# Current_Sens.net
KiCad netlist of a schematic drawn in Altium Designer
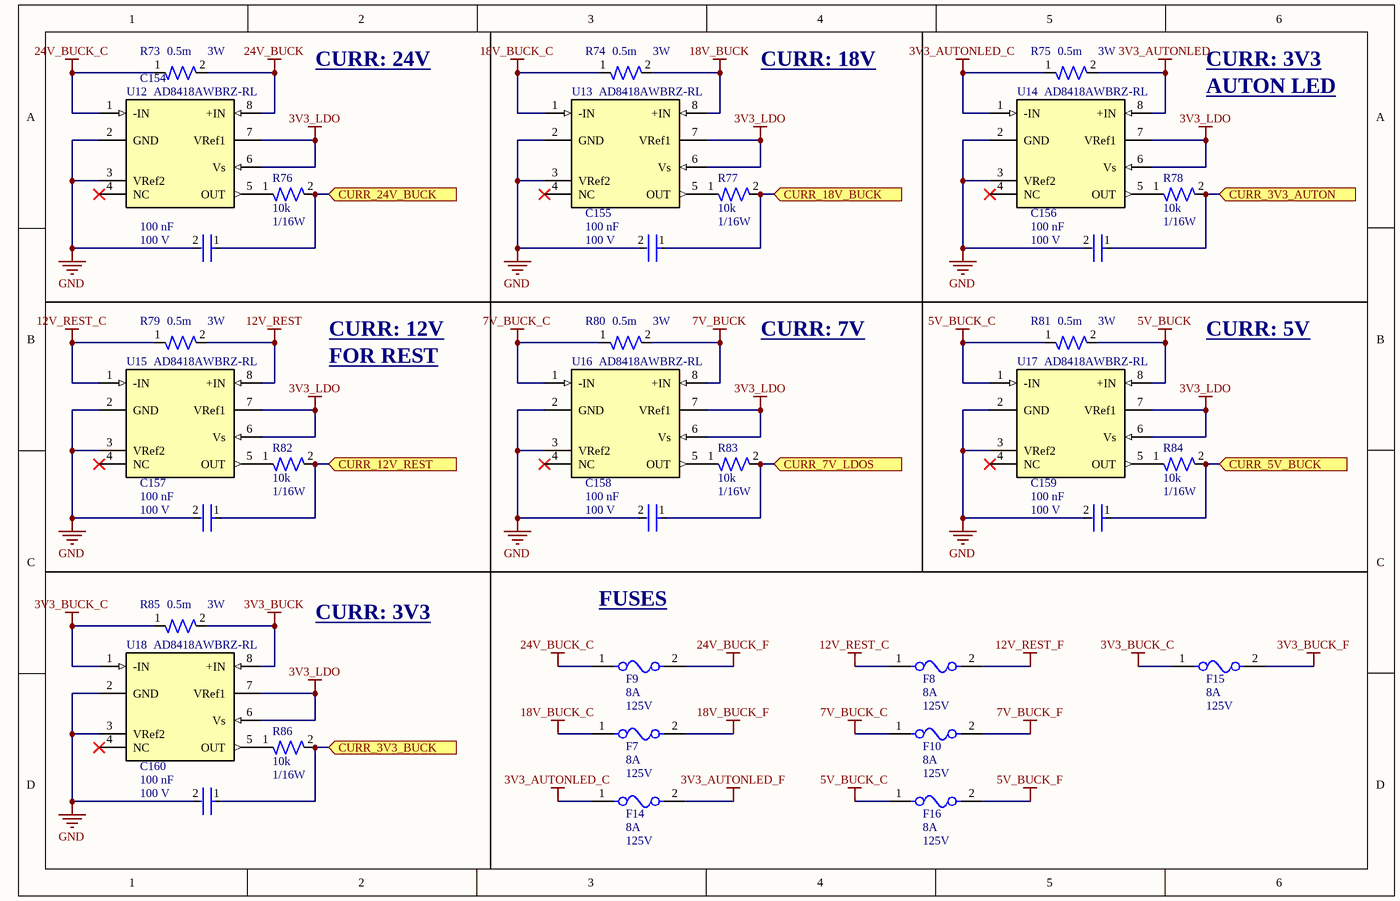
[diagram p0: Current_Sens.SchDoc]

(export (version "E")
  (design (tool "Eeschema 10.0.6"))
  (components
    (comp (ref "C154")
      (value "CC0603KRX7R0BB104")
      (footprint "CAP-0603")
      (description "CAP CER 0.1UF 100V X7R 0603")
      (fields (field (name "CAPACITANCE") "100 nF") (field (name "VOLTAGE") "100 V"))
      (libsource (lib "JLC_25") (part "CAP-100N-0001"))
    )
    (comp (ref "C155")
      (value "CC0603KRX7R0BB104")
      (footprint "CAP-0603")
      (description "CAP CER 0.1UF 100V X7R 0603")
      (fields (field (name "CAPACITANCE") "100 nF") (field (name "VOLTAGE") "100 V"))
      (libsource (lib "JLC_25") (part "CAP-100N-0001"))
    )
    (comp (ref "C156")
      (value "CC0603KRX7R0BB104")
      (footprint "CAP-0603")
      (description "CAP CER 0.1UF 100V X7R 0603")
      (fields (field (name "CAPACITANCE") "100 nF") (field (name "VOLTAGE") "100 V"))
      (libsource (lib "JLC_25") (part "CAP-100N-0001"))
    )
    (comp (ref "C157")
      (value "CC0603KRX7R0BB104")
      (footprint "CAP-0603")
      (description "CAP CER 0.1UF 100V X7R 0603")
      (fields (field (name "CAPACITANCE") "100 nF") (field (name "VOLTAGE") "100 V"))
      (libsource (lib "JLC_25") (part "CAP-100N-0001"))
    )
    (comp (ref "C158")
      (value "CC0603KRX7R0BB104")
      (footprint "CAP-0603")
      (description "CAP CER 0.1UF 100V X7R 0603")
      (fields (field (name "CAPACITANCE") "100 nF") (field (name "VOLTAGE") "100 V"))
      (libsource (lib "JLC_25") (part "CAP-100N-0001"))
    )
    (comp (ref "C159")
      (value "CC0603KRX7R0BB104")
      (footprint "CAP-0603")
      (description "CAP CER 0.1UF 100V X7R 0603")
      (fields (field (name "CAPACITANCE") "100 nF") (field (name "VOLTAGE") "100 V"))
      (libsource (lib "JLC_25") (part "CAP-100N-0001"))
    )
    (comp (ref "C160")
      (value "CC0603KRX7R0BB104")
      (footprint "CAP-0603")
      (description "CAP CER 0.1UF 100V X7R 0603")
      (fields (field (name "CAPACITANCE") "100 nF") (field (name "VOLTAGE") "100 V"))
      (libsource (lib "JLC_25") (part "CAP-100N-0001"))
    )
    (comp (ref "F7")
      (value "01550900M")
      (footprint "FUSE-0001")
      (description "FUSE BLOK CARTRIDGE 125V 10A SMD")
      (fields (field (name "FUSE CURRENT") "8A") (field (name "VOLTAGE RATING") "125V"))
      (libsource (lib "JLC_25") (part "FUSE-0001"))
    )
    (comp (ref "F8")
      (value "01550900M")
      (footprint "FUSE-0001")
      (description "FUSE BLOK CARTRIDGE 125V 10A SMD")
      (fields (field (name "FUSE CURRENT") "8A") (field (name "VOLTAGE RATING") "125V"))
      (libsource (lib "JLC_25") (part "FUSE-0001"))
    )
    (comp (ref "F9")
      (value "01550900M")
      (footprint "FUSE-0001")
      (description "FUSE BLOK CARTRIDGE 125V 10A SMD")
      (fields (field (name "FUSE CURRENT") "8A") (field (name "VOLTAGE RATING") "125V"))
      (libsource (lib "JLC_25") (part "FUSE-0001"))
    )
    (comp (ref "F10")
      (value "01550900M")
      (footprint "FUSE-0001")
      (description "FUSE BLOK CARTRIDGE 125V 10A SMD")
      (fields (field (name "FUSE CURRENT") "8A") (field (name "VOLTAGE RATING") "125V"))
      (libsource (lib "JLC_25") (part "FUSE-0001"))
    )
    (comp (ref "F14")
      (value "01550900M")
      (footprint "FUSE-0001")
      (description "FUSE BLOK CARTRIDGE 125V 10A SMD")
      (fields (field (name "FUSE CURRENT") "8A") (field (name "VOLTAGE RATING") "125V"))
      (libsource (lib "JLC_25") (part "FUSE-0001"))
    )
    (comp (ref "F15")
      (value "01550900M")
      (footprint "FUSE-0001")
      (description "FUSE BLOK CARTRIDGE 125V 10A SMD")
      (fields (field (name "FUSE CURRENT") "8A") (field (name "VOLTAGE RATING") "125V"))
      (libsource (lib "JLC_25") (part "FUSE-0001"))
    )
    (comp (ref "F16")
      (value "01550900M")
      (footprint "FUSE-0001")
      (description "FUSE BLOK CARTRIDGE 125V 10A SMD")
      (fields (field (name "FUSE CURRENT") "8A") (field (name "VOLTAGE RATING") "125V"))
      (libsource (lib "JLC_25") (part "FUSE-0001"))
    )
    (comp (ref "R73")
      (value "CSNL2512FTL500")
      (footprint "RES-2512")
      (description "2512 Chip Resistor - Surface Mount ROHS")
      (fields (field (name "TOLERANCE") "1%") (field (name "POWER") "3W") (field (name "RESISTANCE") "0.5m"))
      (libsource (lib "JLC_25") (part "RES-0.5m-0001"))
    )
    (comp (ref "R74")
      (value "CSNL2512FTL500")
      (footprint "RES-2512")
      (description "2512 Chip Resistor - Surface Mount ROHS")
      (fields (field (name "TOLERANCE") "1%") (field (name "POWER") "3W") (field (name "RESISTANCE") "0.5m"))
      (libsource (lib "JLC_25") (part "RES-0.5m-0001"))
    )
    (comp (ref "R75")
      (value "CSNL2512FTL500")
      (footprint "RES-2512")
      (description "2512 Chip Resistor - Surface Mount ROHS")
      (fields (field (name "TOLERANCE") "1%") (field (name "POWER") "3W") (field (name "RESISTANCE") "0.5m"))
      (libsource (lib "JLC_25") (part "RES-0.5m-0001"))
    )
    (comp (ref "R76")
      (value "RC0402FR-0710KL")
      (footprint "RES-0402")
      (description "RES 10K OHM 1% 1/16W 0402")
      (fields
        (field (name "TOLERANCE") "1%")
        (field (name "RESISTANCE") "10k")
        (field (name "POWER") "1/16W")
      )
      (libsource (lib "JLC_25") (part "RES-10k-0001"))
    )
    (comp (ref "R77")
      (value "RC0402FR-0710KL")
      (footprint "RES-0402")
      (description "RES 10K OHM 1% 1/16W 0402")
      (fields
        (field (name "TOLERANCE") "1%")
        (field (name "RESISTANCE") "10k")
        (field (name "POWER") "1/16W")
      )
      (libsource (lib "JLC_25") (part "RES-10k-0001"))
    )
    (comp (ref "R78")
      (value "RC0402FR-0710KL")
      (footprint "RES-0402")
      (description "RES 10K OHM 1% 1/16W 0402")
      (fields
        (field (name "TOLERANCE") "1%")
        (field (name "RESISTANCE") "10k")
        (field (name "POWER") "1/16W")
      )
      (libsource (lib "JLC_25") (part "RES-10k-0001"))
    )
    (comp (ref "R79")
      (value "CSNL2512FTL500")
      (footprint "RES-2512")
      (description "2512 Chip Resistor - Surface Mount ROHS")
      (fields (field (name "TOLERANCE") "1%") (field (name "POWER") "3W") (field (name "RESISTANCE") "0.5m"))
      (libsource (lib "JLC_25") (part "RES-0.5m-0001"))
    )
    (comp (ref "R80")
      (value "CSNL2512FTL500")
      (footprint "RES-2512")
      (description "2512 Chip Resistor - Surface Mount ROHS")
      (fields (field (name "TOLERANCE") "1%") (field (name "POWER") "3W") (field (name "RESISTANCE") "0.5m"))
      (libsource (lib "JLC_25") (part "RES-0.5m-0001"))
    )
    (comp (ref "R81")
      (value "CSNL2512FTL500")
      (footprint "RES-2512")
      (description "2512 Chip Resistor - Surface Mount ROHS")
      (fields (field (name "TOLERANCE") "1%") (field (name "POWER") "3W") (field (name "RESISTANCE") "0.5m"))
      (libsource (lib "JLC_25") (part "RES-0.5m-0001"))
    )
    (comp (ref "R82")
      (value "RC0402FR-0710KL")
      (footprint "RES-0402")
      (description "RES 10K OHM 1% 1/16W 0402")
      (fields
        (field (name "TOLERANCE") "1%")
        (field (name "RESISTANCE") "10k")
        (field (name "POWER") "1/16W")
      )
      (libsource (lib "JLC_25") (part "RES-10k-0001"))
    )
    (comp (ref "R83")
      (value "RC0402FR-0710KL")
      (footprint "RES-0402")
      (description "RES 10K OHM 1% 1/16W 0402")
      (fields
        (field (name "TOLERANCE") "1%")
        (field (name "RESISTANCE") "10k")
        (field (name "POWER") "1/16W")
      )
      (libsource (lib "JLC_25") (part "RES-10k-0001"))
    )
    (comp (ref "R84")
      (value "RC0402FR-0710KL")
      (footprint "RES-0402")
      (description "RES 10K OHM 1% 1/16W 0402")
      (fields
        (field (name "TOLERANCE") "1%")
        (field (name "RESISTANCE") "10k")
        (field (name "POWER") "1/16W")
      )
      (libsource (lib "JLC_25") (part "RES-10k-0001"))
    )
    (comp (ref "R85")
      (value "CSNL2512FTL500")
      (footprint "RES-2512")
      (description "2512 Chip Resistor - Surface Mount ROHS")
      (fields (field (name "TOLERANCE") "1%") (field (name "POWER") "3W") (field (name "RESISTANCE") "0.5m"))
      (libsource (lib "JLC_25") (part "RES-0.5m-0001"))
    )
    (comp (ref "R86")
      (value "RC0402FR-0710KL")
      (footprint "RES-0402")
      (description "RES 10K OHM 1% 1/16W 0402")
      (fields
        (field (name "TOLERANCE") "1%")
        (field (name "RESISTANCE") "10k")
        (field (name "POWER") "1/16W")
      )
      (libsource (lib "JLC_25") (part "RES-10k-0001"))
    )
    (comp (ref "U12")
      (value "AD8418AWBRZ-RL")
      (footprint "IC-CURR")
      (description "Current Sense Amplifier 1 Circuit 8-MSOP")
      (libsource (lib "JLC_25") (part "IC-CURR-0001"))
    )
    (comp (ref "U13")
      (value "AD8418AWBRZ-RL")
      (footprint "IC-CURR")
      (description "Current Sense Amplifier 1 Circuit 8-MSOP")
      (libsource (lib "JLC_25") (part "IC-CURR-0001"))
    )
    (comp (ref "U14")
      (value "AD8418AWBRZ-RL")
      (footprint "IC-CURR")
      (description "Current Sense Amplifier 1 Circuit 8-MSOP")
      (libsource (lib "JLC_25") (part "IC-CURR-0001"))
    )
    (comp (ref "U15")
      (value "AD8418AWBRZ-RL")
      (footprint "IC-CURR")
      (description "Current Sense Amplifier 1 Circuit 8-MSOP")
      (libsource (lib "JLC_25") (part "IC-CURR-0001"))
    )
    (comp (ref "U16")
      (value "AD8418AWBRZ-RL")
      (footprint "IC-CURR")
      (description "Current Sense Amplifier 1 Circuit 8-MSOP")
      (libsource (lib "JLC_25") (part "IC-CURR-0001"))
    )
    (comp (ref "U17")
      (value "AD8418AWBRZ-RL")
      (footprint "IC-CURR")
      (description "Current Sense Amplifier 1 Circuit 8-MSOP")
      (libsource (lib "JLC_25") (part "IC-CURR-0001"))
    )
    (comp (ref "U18")
      (value "AD8418AWBRZ-RL")
      (footprint "IC-CURR")
      (description "Current Sense Amplifier 1 Circuit 8-MSOP")
      (libsource (lib "JLC_25") (part "IC-CURR-0001"))
    )
  )
  (nets
    (net (code "1") (name "/CURR_3V3_AUTON") (class "Default")
      (node (ref "C156") (pin "1") (pinfunction "1_1") (pintype "passive"))
      (node (ref "R78") (pin "2") (pinfunction "2_2") (pintype "passive"))
    )
    (net (code "2") (name "/CURR_3V3_BUCK") (class "Default")
      (node (ref "C160") (pin "1") (pinfunction "1_1") (pintype "passive"))
      (node (ref "R86") (pin "2") (pinfunction "2_2") (pintype "passive"))
    )
    (net (code "3") (name "/CURR_5V_BUCK") (class "Default")
      (node (ref "C159") (pin "1") (pinfunction "1_1") (pintype "passive"))
      (node (ref "R84") (pin "2") (pinfunction "2_2") (pintype "passive"))
    )
    (net (code "4") (name "/CURR_7V_LDOS") (class "Default")
      (node (ref "C158") (pin "1") (pinfunction "1_1") (pintype "passive"))
      (node (ref "R83") (pin "2") (pinfunction "2_2") (pintype "passive"))
    )
    (net (code "5") (name "/CURR_12V_REST") (class "Default")
      (node (ref "C157") (pin "1") (pinfunction "1_1") (pintype "passive"))
      (node (ref "R82") (pin "2") (pinfunction "2_2") (pintype "passive"))
    )
    (net (code "6") (name "/CURR_18V_BUCK") (class "Default")
      (node (ref "C155") (pin "1") (pinfunction "1_1") (pintype "passive"))
      (node (ref "R77") (pin "2") (pinfunction "2_2") (pintype "passive"))
    )
    (net (code "7") (name "/CURR_24V_BUCK") (class "Default")
      (node (ref "C154") (pin "1") (pinfunction "1_1") (pintype "passive"))
      (node (ref "R76") (pin "2") (pinfunction "2_2") (pintype "passive"))
    )
    (net (code "8") (name "3V3_AUTONLED") (class "Default")
      (node (ref "R75") (pin "2") (pinfunction "2_2") (pintype "passive"))
      (node (ref "U14") (pin "8") (pinfunction "+IN_8") (pintype "input"))
    )
    (net (code "9") (name "3V3_AUTONLED_C") (class "Default")
      (node (ref "F14") (pin "1") (pinfunction "1_1") (pintype "passive"))
      (node (ref "R75") (pin "1") (pinfunction "1_1") (pintype "passive"))
      (node (ref "U14") (pin "1") (pinfunction "-IN_1") (pintype "input"))
    )
    (net (code "10") (name "3V3_AUTONLED_F") (class "Default")
      (node (ref "F14") (pin "2") (pinfunction "2_2") (pintype "passive"))
    )
    (net (code "11") (name "3V3_BUCK") (class "Default")
      (node (ref "R85") (pin "2") (pinfunction "2_2") (pintype "passive"))
      (node (ref "U18") (pin "8") (pinfunction "+IN_8") (pintype "input"))
    )
    (net (code "12") (name "3V3_BUCK_C") (class "Default")
      (node (ref "F15") (pin "1") (pinfunction "1_1") (pintype "passive"))
      (node (ref "R85") (pin "1") (pinfunction "1_1") (pintype "passive"))
      (node (ref "U18") (pin "1") (pinfunction "-IN_1") (pintype "input"))
    )
    (net (code "13") (name "3V3_BUCK_F") (class "Default")
      (node (ref "F15") (pin "2") (pinfunction "2_2") (pintype "passive"))
    )
    (net (code "14") (name "3V3_LDO") (class "Default")
      (node (ref "U12") (pin "6") (pinfunction "Vs_6") (pintype "input"))
      (node (ref "U12") (pin "7") (pinfunction "VRef1_7") (pintype "power_in"))
      (node (ref "U13") (pin "6") (pinfunction "Vs_6") (pintype "input"))
      (node (ref "U13") (pin "7") (pinfunction "VRef1_7") (pintype "power_in"))
      (node (ref "U14") (pin "6") (pinfunction "Vs_6") (pintype "input"))
      (node (ref "U14") (pin "7") (pinfunction "VRef1_7") (pintype "power_in"))
      (node (ref "U15") (pin "6") (pinfunction "Vs_6") (pintype "input"))
      (node (ref "U15") (pin "7") (pinfunction "VRef1_7") (pintype "power_in"))
      (node (ref "U16") (pin "6") (pinfunction "Vs_6") (pintype "input"))
      (node (ref "U16") (pin "7") (pinfunction "VRef1_7") (pintype "power_in"))
      (node (ref "U17") (pin "6") (pinfunction "Vs_6") (pintype "input"))
      (node (ref "U17") (pin "7") (pinfunction "VRef1_7") (pintype "power_in"))
      (node (ref "U18") (pin "6") (pinfunction "Vs_6") (pintype "input"))
      (node (ref "U18") (pin "7") (pinfunction "VRef1_7") (pintype "power_in"))
    )
    (net (code "15") (name "5V_BUCK") (class "Default")
      (node (ref "R81") (pin "2") (pinfunction "2_2") (pintype "passive"))
      (node (ref "U17") (pin "8") (pinfunction "+IN_8") (pintype "input"))
    )
    (net (code "16") (name "5V_BUCK_C") (class "Default")
      (node (ref "F16") (pin "1") (pinfunction "1_1") (pintype "passive"))
      (node (ref "R81") (pin "1") (pinfunction "1_1") (pintype "passive"))
      (node (ref "U17") (pin "1") (pinfunction "-IN_1") (pintype "input"))
    )
    (net (code "17") (name "5V_BUCK_F") (class "Default")
      (node (ref "F16") (pin "2") (pinfunction "2_2") (pintype "passive"))
    )
    (net (code "18") (name "7V_BUCK") (class "Default")
      (node (ref "R80") (pin "2") (pinfunction "2_2") (pintype "passive"))
      (node (ref "U16") (pin "8") (pinfunction "+IN_8") (pintype "input"))
    )
    (net (code "19") (name "7V_BUCK_C") (class "Default")
      (node (ref "F10") (pin "1") (pinfunction "1_1") (pintype "passive"))
      (node (ref "R80") (pin "1") (pinfunction "1_1") (pintype "passive"))
      (node (ref "U16") (pin "1") (pinfunction "-IN_1") (pintype "input"))
    )
    (net (code "20") (name "7V_BUCK_F") (class "Default")
      (node (ref "F10") (pin "2") (pinfunction "2_2") (pintype "passive"))
    )
    (net (code "21") (name "12V_REST") (class "Default")
      (node (ref "R79") (pin "2") (pinfunction "2_2") (pintype "passive"))
      (node (ref "U15") (pin "8") (pinfunction "+IN_8") (pintype "input"))
    )
    (net (code "22") (name "12V_REST_C") (class "Default")
      (node (ref "F8") (pin "1") (pinfunction "1_1") (pintype "passive"))
      (node (ref "R79") (pin "1") (pinfunction "1_1") (pintype "passive"))
      (node (ref "U15") (pin "1") (pinfunction "-IN_1") (pintype "input"))
    )
    (net (code "23") (name "12V_REST_F") (class "Default")
      (node (ref "F8") (pin "2") (pinfunction "2_2") (pintype "passive"))
    )
    (net (code "24") (name "18V_BUCK") (class "Default")
      (node (ref "R74") (pin "2") (pinfunction "2_2") (pintype "passive"))
      (node (ref "U13") (pin "8") (pinfunction "+IN_8") (pintype "input"))
    )
    (net (code "25") (name "18V_BUCK_C") (class "Default")
      (node (ref "F7") (pin "1") (pinfunction "1_1") (pintype "passive"))
      (node (ref "R74") (pin "1") (pinfunction "1_1") (pintype "passive"))
      (node (ref "U13") (pin "1") (pinfunction "-IN_1") (pintype "input"))
    )
    (net (code "26") (name "18V_BUCK_F") (class "Default")
      (node (ref "F7") (pin "2") (pinfunction "2_2") (pintype "passive"))
    )
    (net (code "27") (name "24V_BUCK") (class "Default")
      (node (ref "R73") (pin "2") (pinfunction "2_2") (pintype "passive"))
      (node (ref "U12") (pin "8") (pinfunction "+IN_8") (pintype "input"))
    )
    (net (code "28") (name "24V_BUCK_C") (class "Default")
      (node (ref "F9") (pin "1") (pinfunction "1_1") (pintype "passive"))
      (node (ref "R73") (pin "1") (pinfunction "1_1") (pintype "passive"))
      (node (ref "U12") (pin "1") (pinfunction "-IN_1") (pintype "input"))
    )
    (net (code "29") (name "24V_BUCK_F") (class "Default")
      (node (ref "F9") (pin "2") (pinfunction "2_2") (pintype "passive"))
    )
    (net (code "30") (name "GND") (class "Default")
      (node (ref "C154") (pin "2") (pinfunction "2_2") (pintype "passive"))
      (node (ref "C155") (pin "2") (pinfunction "2_2") (pintype "passive"))
      (node (ref "C156") (pin "2") (pinfunction "2_2") (pintype "passive"))
      (node (ref "C157") (pin "2") (pinfunction "2_2") (pintype "passive"))
      (node (ref "C158") (pin "2") (pinfunction "2_2") (pintype "passive"))
      (node (ref "C159") (pin "2") (pinfunction "2_2") (pintype "passive"))
      (node (ref "C160") (pin "2") (pinfunction "2_2") (pintype "passive"))
      (node (ref "U12") (pin "2") (pinfunction "GND_2") (pintype "power_in"))
      (node (ref "U12") (pin "3") (pinfunction "VRef2_3") (pintype "passive"))
      (node (ref "U13") (pin "2") (pinfunction "GND_2") (pintype "power_in"))
      (node (ref "U13") (pin "3") (pinfunction "VRef2_3") (pintype "passive"))
      (node (ref "U14") (pin "2") (pinfunction "GND_2") (pintype "power_in"))
      (node (ref "U14") (pin "3") (pinfunction "VRef2_3") (pintype "passive"))
      (node (ref "U15") (pin "2") (pinfunction "GND_2") (pintype "power_in"))
      (node (ref "U15") (pin "3") (pinfunction "VRef2_3") (pintype "passive"))
      (node (ref "U16") (pin "2") (pinfunction "GND_2") (pintype "power_in"))
      (node (ref "U16") (pin "3") (pinfunction "VRef2_3") (pintype "passive"))
      (node (ref "U17") (pin "2") (pinfunction "GND_2") (pintype "power_in"))
      (node (ref "U17") (pin "3") (pinfunction "VRef2_3") (pintype "passive"))
      (node (ref "U18") (pin "2") (pinfunction "GND_2") (pintype "power_in"))
      (node (ref "U18") (pin "3") (pinfunction "VRef2_3") (pintype "passive"))
    )
    (net (code "31") (name "Net-(U12-OUT)") (class "Default")
      (node (ref "R76") (pin "1") (pinfunction "1_1") (pintype "passive"))
      (node (ref "U12") (pin "5") (pinfunction "OUT_5") (pintype "output"))
    )
    (net (code "32") (name "Net-(U13-OUT)") (class "Default")
      (node (ref "R77") (pin "1") (pinfunction "1_1") (pintype "passive"))
      (node (ref "U13") (pin "5") (pinfunction "OUT_5") (pintype "output"))
    )
    (net (code "33") (name "Net-(U14-OUT)") (class "Default")
      (node (ref "R78") (pin "1") (pinfunction "1_1") (pintype "passive"))
      (node (ref "U14") (pin "5") (pinfunction "OUT_5") (pintype "output"))
    )
    (net (code "34") (name "Net-(U15-OUT)") (class "Default")
      (node (ref "R82") (pin "1") (pinfunction "1_1") (pintype "passive"))
      (node (ref "U15") (pin "5") (pinfunction "OUT_5") (pintype "output"))
    )
    (net (code "35") (name "Net-(U16-OUT)") (class "Default")
      (node (ref "R83") (pin "1") (pinfunction "1_1") (pintype "passive"))
      (node (ref "U16") (pin "5") (pinfunction "OUT_5") (pintype "output"))
    )
    (net (code "36") (name "Net-(U17-OUT)") (class "Default")
      (node (ref "R84") (pin "1") (pinfunction "1_1") (pintype "passive"))
      (node (ref "U17") (pin "5") (pinfunction "OUT_5") (pintype "output"))
    )
    (net (code "37") (name "Net-(U18-OUT)") (class "Default")
      (node (ref "R86") (pin "1") (pinfunction "1_1") (pintype "passive"))
      (node (ref "U18") (pin "5") (pinfunction "OUT_5") (pintype "output"))
    )
    (net (code "38") (name "unconnected-(U12-NC-Pad4)") (class "Default")
      (node (ref "U12") (pin "4") (pinfunction "NC_4") (pintype "passive+no_connect"))
    )
    (net (code "39") (name "unconnected-(U13-NC-Pad4)") (class "Default")
      (node (ref "U13") (pin "4") (pinfunction "NC_4") (pintype "passive+no_connect"))
    )
    (net (code "40") (name "unconnected-(U14-NC-Pad4)") (class "Default")
      (node (ref "U14") (pin "4") (pinfunction "NC_4") (pintype "passive+no_connect"))
    )
    (net (code "41") (name "unconnected-(U15-NC-Pad4)") (class "Default")
      (node (ref "U15") (pin "4") (pinfunction "NC_4") (pintype "passive+no_connect"))
    )
    (net (code "42") (name "unconnected-(U16-NC-Pad4)") (class "Default")
      (node (ref "U16") (pin "4") (pinfunction "NC_4") (pintype "passive+no_connect"))
    )
    (net (code "43") (name "unconnected-(U17-NC-Pad4)") (class "Default")
      (node (ref "U17") (pin "4") (pinfunction "NC_4") (pintype "passive+no_connect"))
    )
    (net (code "44") (name "unconnected-(U18-NC-Pad4)") (class "Default")
      (node (ref "U18") (pin "4") (pinfunction "NC_4") (pintype "passive+no_connect"))
    )
  )
)
